# Voeding.net
KiCad netlist of a schematic drawn in Altium Designer
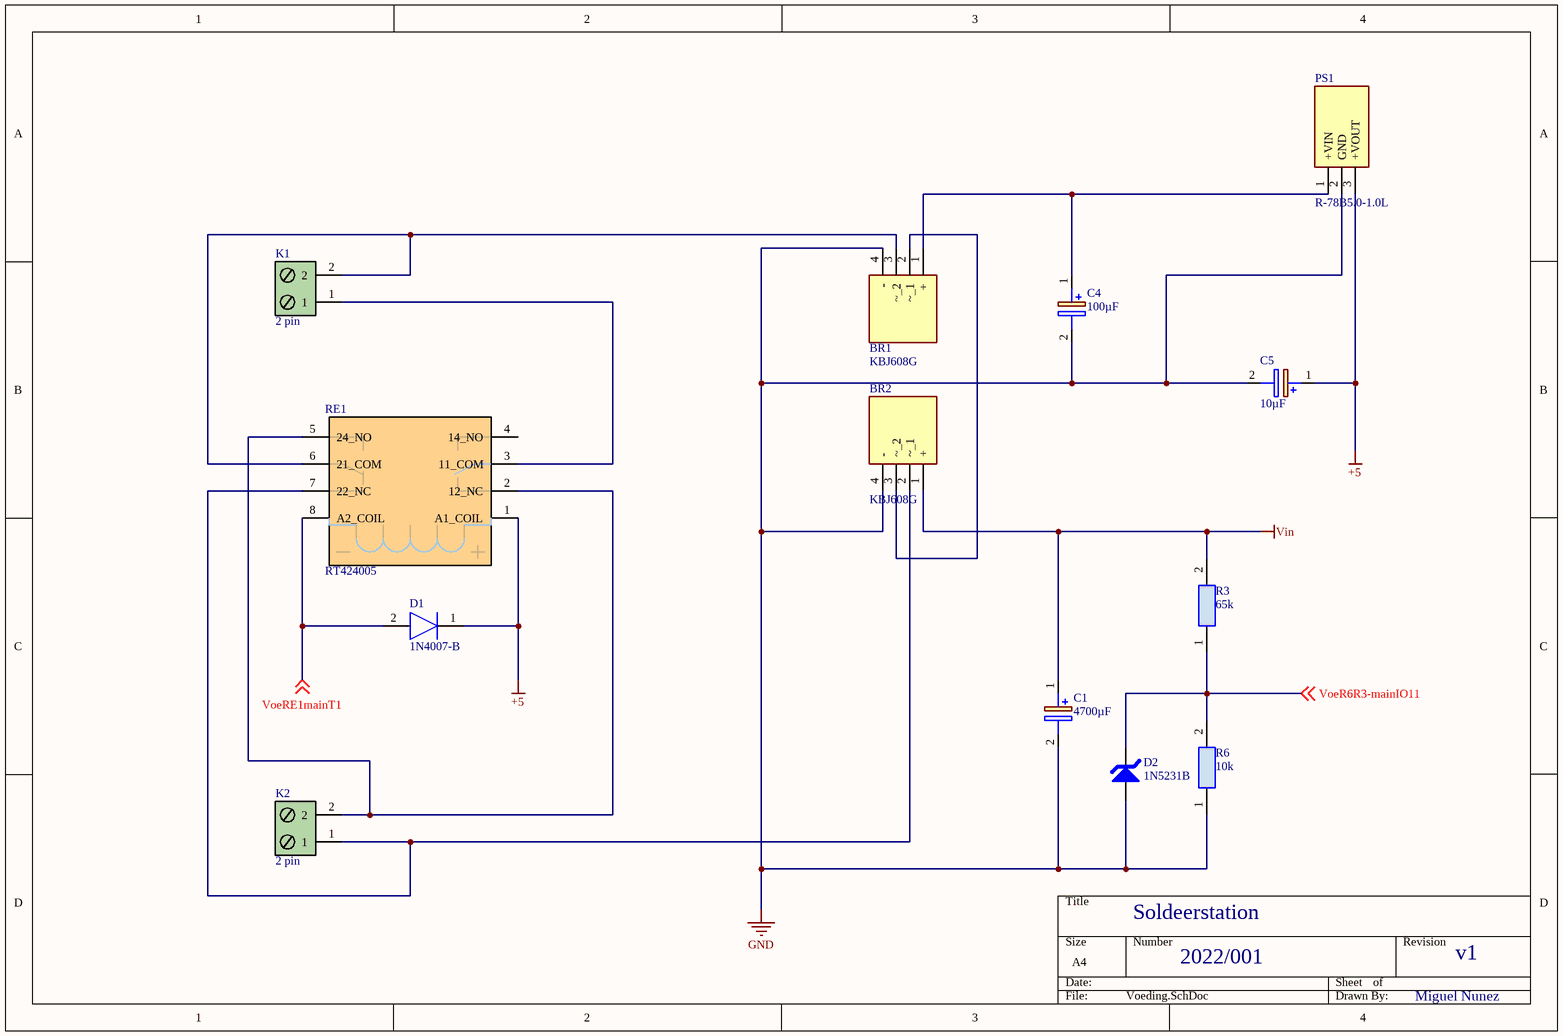
[diagram p0: Voeding.SchDoc]

(export (version "E")
  (design (tool "Eeschema 10.0.6"))
  (components
    (comp (ref "BR1")
      (value "KBJ608G")
      (footprint "SamacSys:TO750P480X2500X1900-4P")
      (description "Bridge Rectifier")
      (fields (field (name "MOUSER2 PART NUMBER") "621-KBJ608G"))
      (libsource (lib "PO_SS_Lib") (part "KBJ608G"))
    )
    (comp (ref "BR2")
      (value "KBJ608G")
      (footprint "SamacSys:TO750P480X2500X1900-4P")
      (description "Bridge Rectifier")
      (fields (field (name "MOUSER2 PART NUMBER") "621-KBJ608G"))
      (libsource (lib "") (part "KBJ608G_1"))
    )
    (comp (ref "C1")
      (value "4700µF")
      (footprint "WCAP-ATG8_D22H41")
      (description "Capacitor Polarised ESK478M050AQ3AA")
      (fields
        (field (name "MOUSER2 PART NUMBER") "80-ESK478M050AQ3AA")
        (field (name "MANUFACTURER_PART_NUMBER") "ESK478M050AQ3AA")
      )
      (libsource (lib "PO_SS_Lib") (part "ELCAP 4700µF"))
    )
    (comp (ref "C4")
      (value "100µF")
      (footprint "WCAP-AT1H_D10H16")
      (description "Capacitor Polarised 100µF Wurth 860241181006")
      (fields (field (name "MANUFACTURER_PART_NUMBER") "860241181006"))
      (libsource (lib "PO_SS_Lib") (part "ELCAP 100µF"))
    )
    (comp (ref "C5")
      (value "10µF")
      (footprint "WCAP-AT1H_D5H11")
      (description "Capacitor Polarised Wurth Elektronik 860240672002 10µF")
      (fields (field (name "MANUFACTURER_PART_NUMBER") "860240672002"))
      (libsource (lib "PO_SS_Lib") (part "ELCAP 10µF"))
    )
    (comp (ref "D1")
      (value "1N4007-B")
      (footprint "SamacSys:DIOAD1410W90L470D235")
      (description "Diode 1N4007-B 1000V, 1A")
      (libsource (lib "PO_SS_Lib") (part "D 1N4007-B"))
    )
    (comp (ref "D2")
      (value "1N5231B")
      (footprint "DIOAD1165W56L425D185")
      (description "Zenerdiode 1N5231B 5.1V 500mW")
      (fields (field (name "COPYRIGHT") "Copyright (C) 2022 Ultra Librarian. All rights reserved."))
      (libsource (lib "PO_SS_Lib") (part "ZD 1N5231B"))
    )
    (comp (ref "K1")
      (value "2 pin")
      (footprint "SamacSys:1729128")
      (description "Connector Term. blok. 1729128 2 pin")
      (fields (field (name "MANUFACTURER_PART_NUMBER") "1729128"))
      (libsource (lib "PO_SS_Lib") (part "Term. blok 2 pin"))
    )
    (comp (ref "K2")
      (value "2 pin")
      (footprint "SamacSys:1729128")
      (description "Connector Term. blok. 1729128 2 pin")
      (fields (field (name "MANUFACTURER_PART_NUMBER") "1729128"))
      (libsource (lib "PO_SS_Lib") (part "Term. blok 2 pin"))
    )
    (comp (ref "PS1")
      (value "R-78B5.0-1.0L")
      (footprint "SamacSys:R78B1210L")
      (description "Power Supply DC/DC converter 6.5-34Vin 5Vout")
      (fields (field (name "MOUSER2 PART NUMBER") "919-R-78B5.0-1.0L"))
      (libsource (lib "PO_SS_Lib") (part "R-78B5.0-1.0L"))
    )
    (comp (ref "R3")
      (value "65k")
      (footprint "RESC2012X60N")
      (description "Res Thin Film 0805 68K Ohm 0.1% 1/8W ±25ppm/°C Molded SMD SMD Punched Carrier T/R")
      (fields
        (field (name "MANUFACTURER") "Panasonic")
        (field (name "MANUFACTURER PART NUMBER") "ERA-6AEB683V")
      )
      (libsource (lib "PO_SS_Lib") (part "RES 68k 0805"))
    )
    (comp (ref "R6")
      (value "10k")
      (footprint "SamacSys:RESC2012X60N")
      (description "10k SMD 0805  CR0805-FX-1002ELF")
      (fields
        (field (name "MOUSER2 PART NUMBER") "652-CR0805FX-1002ELF")
        (field (name "MANUFACTURER_PART_NUMBER") "CR0805-FX-1002ELF")
      )
      (libsource (lib "PO_SS_Lib") (part "RES 10k 0805"))
    )
    (comp (ref "RE1")
      (value "RT424005")
      (footprint "SamacSys:RT42")
      (description "Relay or Contactor")
      (fields (field (name "MOUSER2 PART NUMBER") "655-RT424005"))
      (libsource (lib "PO_SS_Lib") (part "RT424005"))
    )
  )
  (nets
    (net (code "1") (name "+5") (class "Default")
      (node (ref "C5") (pin "1") (pinfunction "+_1") (pintype "passive"))
      (node (ref "D1") (pin "1") (pinfunction "K_1") (pintype "passive"))
      (node (ref "PS1") (pin "3") (pinfunction "+VOUT_3") (pintype "passive"))
      (node (ref "RE1") (pin "1") (pinfunction "A1_COIL_1") (pintype "passive"))
    )
    (net (code "2") (name "GND") (class "Default")
      (node (ref "BR1") (pin "4") (pinfunction "-_4") (pintype "passive"))
      (node (ref "BR2") (pin "4") (pinfunction "-_4") (pintype "passive"))
      (node (ref "C1") (pin "2") (pinfunction "-_2") (pintype "passive"))
      (node (ref "C4") (pin "2") (pinfunction "-_2") (pintype "passive"))
      (node (ref "C5") (pin "2") (pinfunction "-_2") (pintype "passive"))
      (node (ref "D2") (pin "2") (pinfunction "2_2") (pintype "passive"))
      (node (ref "PS1") (pin "2") (pinfunction "GND_2") (pintype "passive"))
      (node (ref "R6") (pin "1") (pinfunction "1_1") (pintype "passive"))
    )
    (net (code "3") (name "Net-(BR1-+)") (class "Default")
      (node (ref "BR1") (pin "1") (pinfunction "+_1") (pintype "passive"))
      (node (ref "C4") (pin "1") (pinfunction "+_1") (pintype "passive"))
      (node (ref "PS1") (pin "1") (pinfunction "+VIN_1") (pintype "passive"))
    )
    (net (code "4") (name "Net-(BR1-~_1)") (class "Default")
      (node (ref "BR1") (pin "2") (pinfunction "~_1_2") (pintype "passive"))
      (node (ref "BR2") (pin "3") (pinfunction "~_2_3") (pintype "passive"))
    )
    (net (code "5") (name "Net-(BR1-~_2)") (class "Default")
      (node (ref "BR1") (pin "3") (pinfunction "~_2_3") (pintype "passive"))
      (node (ref "K1") (pin "2") (pinfunction "2_2") (pintype "passive"))
      (node (ref "RE1") (pin "6") (pinfunction "21_COM_6") (pintype "passive"))
    )
    (net (code "6") (name "Net-(BR2-~_1)") (class "Default")
      (node (ref "BR2") (pin "2") (pinfunction "~_1_2") (pintype "passive"))
      (node (ref "K2") (pin "1") (pinfunction "1_1") (pintype "passive"))
      (node (ref "RE1") (pin "7") (pinfunction "22_NC_7") (pintype "passive"))
    )
    (net (code "7") (name "Net-(RE1-11_COM)") (class "Default")
      (node (ref "K1") (pin "1") (pinfunction "1_1") (pintype "passive"))
      (node (ref "RE1") (pin "3") (pinfunction "11_COM_3") (pintype "passive"))
    )
    (net (code "8") (name "Net-(RE1-12_NC)") (class "Default")
      (node (ref "K2") (pin "2") (pinfunction "2_2") (pintype "passive"))
      (node (ref "RE1") (pin "2") (pinfunction "12_NC_2") (pintype "passive"))
      (node (ref "RE1") (pin "5") (pinfunction "24_NO_5") (pintype "passive"))
    )
    (net (code "9") (name "Vin") (class "Default")
      (node (ref "BR2") (pin "1") (pinfunction "+_1") (pintype "passive"))
      (node (ref "C1") (pin "1") (pinfunction "+_1") (pintype "passive"))
      (node (ref "R3") (pin "2") (pinfunction "2_2") (pintype "passive"))
    )
    (net (code "10") (name "VoeR6R3-mainIO11") (class "Default")
      (node (ref "D2") (pin "1") (pinfunction "1_1") (pintype "passive"))
      (node (ref "R3") (pin "1") (pinfunction "1_1") (pintype "passive"))
      (node (ref "R6") (pin "2") (pinfunction "2_2") (pintype "passive"))
    )
    (net (code "11") (name "VoeRE1mainT1") (class "Default")
      (node (ref "D1") (pin "2") (pinfunction "A_2") (pintype "passive"))
      (node (ref "RE1") (pin "8") (pinfunction "A2_COIL_8") (pintype "passive"))
    )
    (net (code "12") (name "unconnected-(RE1-14_NO-Pad4)") (class "Default")
      (node (ref "RE1") (pin "4") (pinfunction "14_NO_4") (pintype "passive"))
    )
  )
)
